# Ethernet.net
KiCad netlist of a schematic drawn in Altium Designer
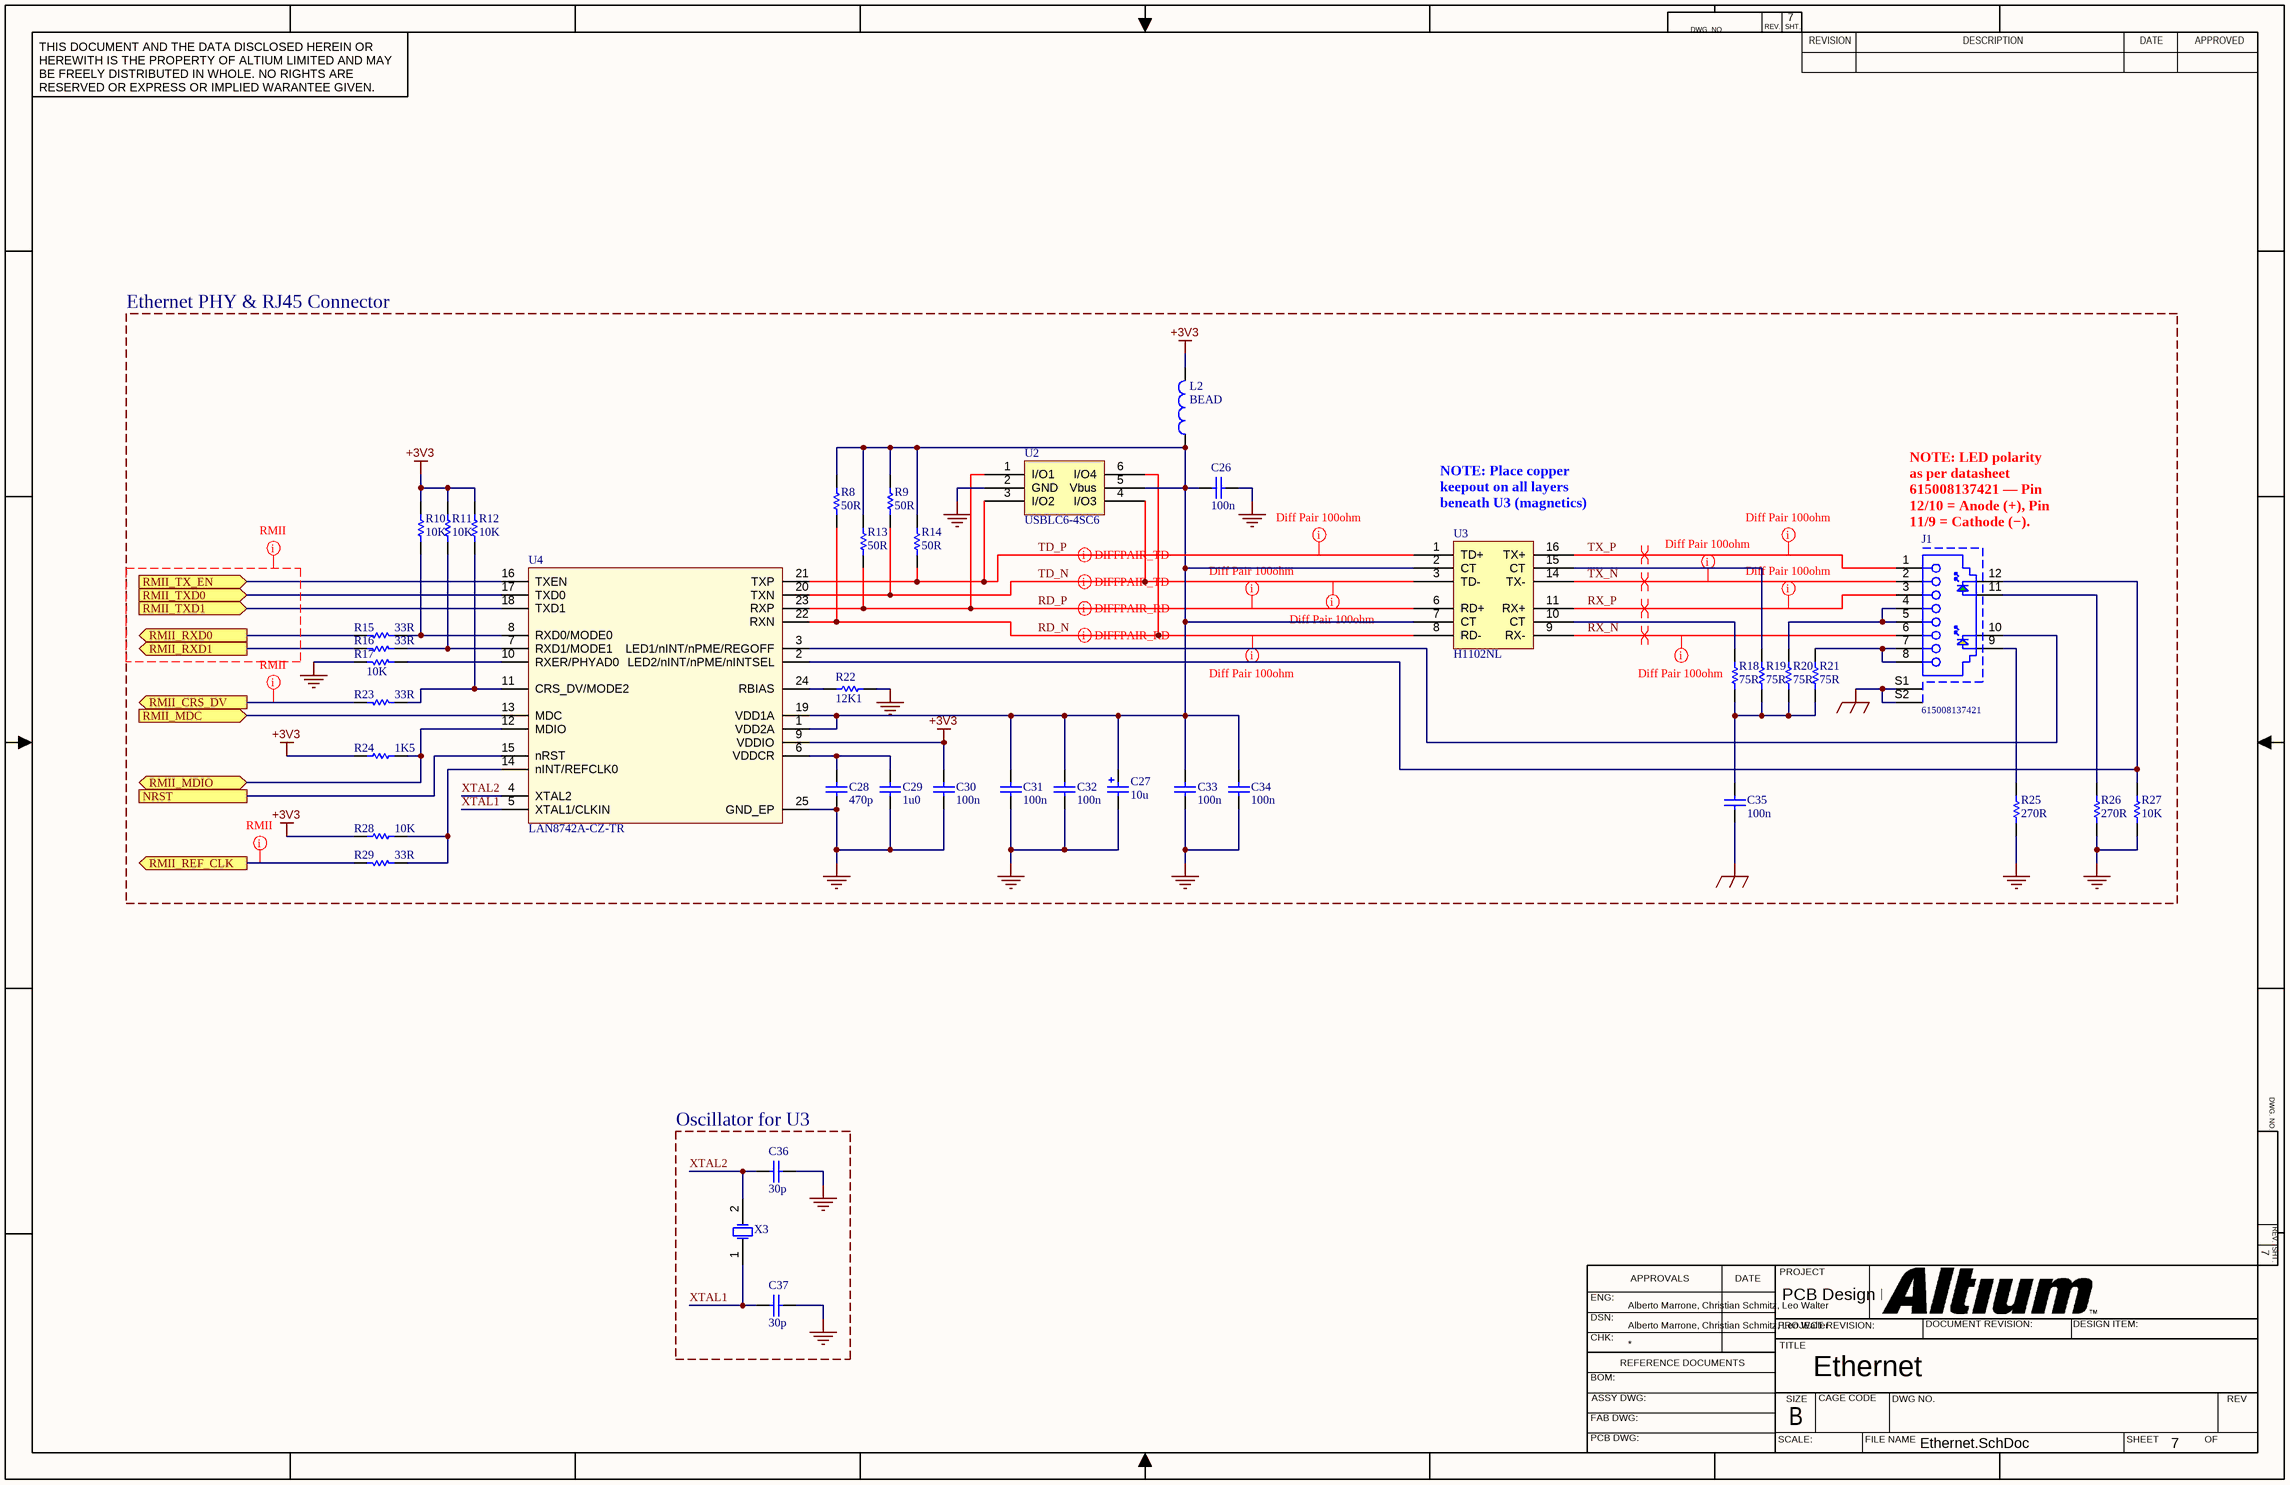
[diagram p0: Ethernet.SchDoc]

(export (version "E")
  (design (tool "Eeschema 10.0.6"))
  (components
    (comp (ref "C26")
      (value "100n")
      (footprint "0603C")
      (description "Capacitor")
      (fields (field (name "PUBLISHER") "Altium Limited"))
      (libsource (lib "Miscellaneous Devices") (part "Cap"))
    )
    (comp (ref "C27")
      (value "10u")
      (footprint "TAN-B")
      (description "Tantalum Capacitor")
      (fields (field (name "PUBLISHER") "Altium Limited"))
      (libsource (lib "Miscellaneous Devices") (part "Cap Pol1"))
    )
    (comp (ref "C28")
      (value "470p")
      (footprint "0603C")
      (description "Capacitor 0402 / 0603 / 0805")
      (libsource (lib "MCD_TOOLS") (part "Capacitor_ST"))
    )
    (comp (ref "C29")
      (value "1u0")
      (footprint "0603C")
      (description "Capacitor")
      (fields (field (name "TOLERANCE") "10%"))
      (libsource (lib "MB963_1") (part "CAP SMD 0603  X5R 1µF 25V 10%"))
    )
    (comp (ref "C30")
      (value "100n")
      (footprint "0603C")
      (description "Capacitor")
      (fields (field (name "PUBLISHER") "Altium Limited"))
      (libsource (lib "Miscellaneous Devices") (part "Cap"))
    )
    (comp (ref "C31")
      (value "100n")
      (footprint "0603C")
      (description "Capacitor")
      (fields (field (name "PUBLISHER") "Altium Limited"))
      (libsource (lib "Miscellaneous Devices") (part "Cap"))
    )
    (comp (ref "C32")
      (value "100n")
      (footprint "0603C")
      (description "Capacitor")
      (fields (field (name "PUBLISHER") "Altium Limited"))
      (libsource (lib "Miscellaneous Devices") (part "Cap"))
    )
    (comp (ref "C33")
      (value "100n")
      (footprint "0603C")
      (description "Capacitor")
      (fields (field (name "PUBLISHER") "Altium Limited"))
      (libsource (lib "Miscellaneous Devices") (part "Cap"))
    )
    (comp (ref "C34")
      (value "100n")
      (footprint "0603C")
      (description "Capacitor")
      (fields (field (name "PUBLISHER") "Altium Limited"))
      (libsource (lib "Miscellaneous Devices") (part "Cap"))
    )
    (comp (ref "C35")
      (value "100n")
      (footprint "0603C")
      (description "Capacitor")
      (fields (field (name "PUBLISHER") "Altium Limited"))
      (libsource (lib "Miscellaneous Devices") (part "Cap"))
    )
    (comp (ref "C36")
      (value "30p")
      (footprint "0603C")
      (description "Capacitor 0402 / 0603 / 0805")
      (libsource (lib "MCD_TOOLS") (part "Capacitor_ST"))
    )
    (comp (ref "C37")
      (value "30p")
      (footprint "0603C")
      (description "Capacitor 0402 / 0603 / 0805")
      (libsource (lib "MCD_TOOLS") (part "Capacitor_ST"))
    )
    (comp (ref "J1")
      (value "615008137421")
      (footprint "615008137421")
      (description "Modular Jack WR-MJ, Tab Up, Shielded, with LED and EMI Panel Finger, Horizontal Entry, THT, 8P8C")
      (fields (field (name "MANUFACTURER") "Wurth Elektronik") (field (name "PUBLISHER") "WurthElektronik"))
      (libsource (lib "Altium Content Vault") (part "WE-CN-1P-2F-J12_A"))
    )
    (comp (ref "L2")
      (value "BEAD")
      (footprint "0603L")
      (description "Inductor")
      (fields (field (name "PUBLISHER") "Altium Limited"))
      (libsource (lib "Miscellaneous Devices") (part "Inductor"))
    )
    (comp (ref "R8")
      (value "50R")
      (footprint "0603R")
      (description "Resistor,50,0603,1%,YAGEO")
      (libsource (lib "MB1137") (part "Res_50_1%_0603"))
    )
    (comp (ref "R9")
      (value "50R")
      (footprint "0603R")
      (description "Resistor,50,0603,1%,YAGEO")
      (libsource (lib "MB1137") (part "Res_50_1%_0603"))
    )
    (comp (ref "R10")
      (value "10K")
      (footprint "0603R")
      (description "Resistor")
      (fields (field (name "PUBLISHER") "Altium Limited"))
      (libsource (lib "Miscellaneous Devices") (part "res1"))
    )
    (comp (ref "R11")
      (value "10K")
      (footprint "0603R")
      (description "Resistor")
      (fields (field (name "PUBLISHER") "Altium Limited"))
      (libsource (lib "Miscellaneous Devices") (part "res1"))
    )
    (comp (ref "R12")
      (value "10K")
      (footprint "0603R")
      (description "Resistor")
      (fields (field (name "PUBLISHER") "Altium Limited"))
      (libsource (lib "Miscellaneous Devices") (part "res1"))
    )
    (comp (ref "R13")
      (value "50R")
      (footprint "0603R")
      (description "Resistor,50,0603,1%,YAGEO")
      (libsource (lib "MB1137") (part "Res_50_1%_0603"))
    )
    (comp (ref "R14")
      (value "50R")
      (footprint "0603R")
      (description "Resistor,50,0603,1%,YAGEO")
      (libsource (lib "MB1137") (part "Res_50_1%_0603"))
    )
    (comp (ref "R15")
      (value "33R")
      (footprint "0603R")
      (description "Resistor")
      (fields (field (name "TOLERANCE") "1%") (field (name "PUBLISHER") "Altium Limited"))
      (libsource (lib "Miscellaneous Devices") (part "res1"))
    )
    (comp (ref "R16")
      (value "33R")
      (footprint "0603R")
      (description "Resistor")
      (fields (field (name "TOLERANCE") "1%") (field (name "PUBLISHER") "Altium Limited"))
      (libsource (lib "Miscellaneous Devices") (part "res1"))
    )
    (comp (ref "R17")
      (value "10K")
      (footprint "0603R")
      (description "Resistor")
      (fields (field (name "PUBLISHER") "Altium Limited"))
      (libsource (lib "Miscellaneous Devices") (part "res1"))
    )
    (comp (ref "R18")
      (value "75R")
      (footprint "0603R")
      (description "Resistor")
      (fields (field (name "TOLERANCE") "1%"))
      (libsource (lib "MB1137") (part "Res_75_1%_0603"))
    )
    (comp (ref "R19")
      (value "75R")
      (footprint "0603R")
      (description "Resistor")
      (fields (field (name "TOLERANCE") "1%"))
      (libsource (lib "MB1137") (part "Res_75_1%_0603"))
    )
    (comp (ref "R20")
      (value "75R")
      (footprint "0603R")
      (description "Resistor")
      (fields (field (name "TOLERANCE") "1%"))
      (libsource (lib "MB1137") (part "Res_75_1%_0603"))
    )
    (comp (ref "R21")
      (value "75R")
      (footprint "0603R")
      (description "Resistor")
      (fields (field (name "TOLERANCE") "1%"))
      (libsource (lib "MB1137") (part "Res_75_1%_0603"))
    )
    (comp (ref "R22")
      (value "12K1")
      (footprint "0603R")
      (description "Resistor,12K1,0603,1%,VISHAY")
      (libsource (lib "MCD_TOOLS") (part "Res_12K1_1%_0603"))
    )
    (comp (ref "R23")
      (value "33R")
      (footprint "0603R")
      (description "Resistor")
      (fields (field (name "TOLERANCE") "1%") (field (name "PUBLISHER") "Altium Limited"))
      (libsource (lib "Miscellaneous Devices") (part "res1"))
    )
    (comp (ref "R24")
      (value "1K5")
      (footprint "0603R")
      (description "Resistor,1K5,0402,1%,YAGEO")
      (libsource (lib "MCD_TOOLS") (part "Res_1K5_1%_0402"))
    )
    (comp (ref "R25")
      (value "270R")
      (footprint "0603R")
      (description "Resistor 0402 / 0603 / 0805")
      (libsource (lib "Miscellaneous Devices") (part "Res1"))
    )
    (comp (ref "R26")
      (value "270R")
      (footprint "0603R")
      (description "Resistor 0402 / 0603 / 0805")
      (libsource (lib "Miscellaneous Devices") (part "Res1"))
    )
    (comp (ref "R27")
      (value "10K")
      (footprint "0603R")
      (description "Resistor")
      (fields (field (name "PUBLISHER") "Altium Limited"))
      (libsource (lib "Miscellaneous Devices") (part "res1"))
    )
    (comp (ref "R28")
      (value "10K")
      (footprint "0603R")
      (description "Resistor")
      (fields (field (name "PUBLISHER") "Altium Limited"))
      (libsource (lib "Miscellaneous Devices") (part "res1"))
    )
    (comp (ref "R29")
      (value "33R")
      (footprint "0603R")
      (description "Resistor")
      (fields (field (name "TOLERANCE") "1%") (field (name "PUBLISHER") "Altium Limited"))
      (libsource (lib "Miscellaneous Devices") (part "res1"))
    )
    (comp (ref "U2")
      (value "USBLC6-4SC6")
      (footprint "SOT23-6L")
      (libsource (lib "MB1137_1") (part "USBLC6-4SC6"))
    )
    (comp (ref "U3")
      (value "H1102NL")
      (footprint "Transformer")
      (description "replaces the KMS-1102NL")
      (libsource (lib "MB1137") (part "KMS-1102NL"))
    )
    (comp (ref "U4")
      (value "LAN8742A-CZ-TR")
      (footprint "QFN24_0R5_4X4")
      (libsource (lib "MB1137") (part "LAN8742A-CZ-TR"))
    )
    (comp (ref "X3")
      (value "ECS-250-12-30Q-JES-TR")
      (footprint "XTAL_2SM_5R0X3R2")
      (description "Crystal Oscillator")
      (fields (field (name "PUBLISHER") "Altium Limited"))
      (libsource (lib "MB1137") (part "XTAL_5032"))
    )
  )
  (nets
    (net (code "1") (name "+3V3") (class "Default")
      (node (ref "C30") (pin "2") (pinfunction "2_2") (pintype "passive"))
      (node (ref "L2") (pin "2") (pinfunction "2_2") (pintype "passive"))
      (node (ref "R10") (pin "1") (pinfunction "1_1") (pintype "passive"))
      (node (ref "R11") (pin "1") (pinfunction "1_1") (pintype "passive"))
      (node (ref "R12") (pin "1") (pinfunction "1_1") (pintype "passive"))
      (node (ref "R24") (pin "2") (pinfunction "2_2") (pintype "passive"))
      (node (ref "R28") (pin "1") (pinfunction "1_1") (pintype "passive"))
      (node (ref "U4") (pin "9") (pinfunction "VDDIO_9") (pintype "passive"))
    )
    (net (code "2") (name "/NRST") (class "Default")
      (node (ref "U4") (pin "15") (pinfunction "nRST_15") (pintype "passive"))
    )
    (net (code "3") (name "/RD_N") (class "Default")
      (node (ref "R8") (pin "1") (pinfunction "1_1") (pintype "passive"))
      (node (ref "U2") (pin "6") (pinfunction "I/O4_6") (pintype "passive"))
      (node (ref "U3") (pin "8") (pinfunction "RD-_8") (pintype "passive"))
      (node (ref "U4") (pin "22") (pinfunction "RXN_22") (pintype "passive"))
    )
    (net (code "4") (name "/RD_P") (class "Default")
      (node (ref "R13") (pin "1") (pinfunction "1_1") (pintype "passive"))
      (node (ref "U2") (pin "1") (pinfunction "I/O1_1") (pintype "passive"))
      (node (ref "U3") (pin "6") (pinfunction "RD+_6") (pintype "passive"))
      (node (ref "U4") (pin "23") (pinfunction "RXP_23") (pintype "passive"))
    )
    (net (code "5") (name "/RMII_CRS_DV") (class "Default")
      (node (ref "R23") (pin "2") (pinfunction "2_2") (pintype "passive"))
    )
    (net (code "6") (name "/RMII_MDC") (class "Default")
      (node (ref "U4") (pin "13") (pinfunction "MDC_13") (pintype "passive"))
    )
    (net (code "7") (name "/RMII_MDIO") (class "Default")
      (node (ref "R24") (pin "1") (pinfunction "1_1") (pintype "passive"))
      (node (ref "U4") (pin "12") (pinfunction "MDIO_12") (pintype "passive"))
    )
    (net (code "8") (name "/RMII_REF_CLK") (class "Default")
      (node (ref "R29") (pin "2") (pinfunction "2_2") (pintype "passive"))
    )
    (net (code "9") (name "/RMII_RXD0") (class "Default")
      (node (ref "R15") (pin "2") (pinfunction "2_2") (pintype "passive"))
    )
    (net (code "10") (name "/RMII_RXD1") (class "Default")
      (node (ref "R16") (pin "2") (pinfunction "2_2") (pintype "passive"))
    )
    (net (code "11") (name "/RMII_TXD0") (class "Default")
      (node (ref "U4") (pin "17") (pinfunction "TXD0_17") (pintype "passive"))
    )
    (net (code "12") (name "/RMII_TXD1") (class "Default")
      (node (ref "U4") (pin "18") (pinfunction "TXD1_18") (pintype "passive"))
    )
    (net (code "13") (name "/RMII_TX_EN") (class "Default")
      (node (ref "U4") (pin "16") (pinfunction "TXEN_16") (pintype "passive"))
    )
    (net (code "14") (name "/RX_N") (class "Default")
      (node (ref "J1") (pin "6") (pinfunction "6_6") (pintype "passive"))
      (node (ref "U3") (pin "9") (pinfunction "RX-_9") (pintype "passive"))
    )
    (net (code "15") (name "/RX_P") (class "Default")
      (node (ref "J1") (pin "3") (pinfunction "3_3") (pintype "passive"))
      (node (ref "U3") (pin "11") (pinfunction "RX+_11") (pintype "passive"))
    )
    (net (code "16") (name "/TD_N") (class "Default")
      (node (ref "R9") (pin "1") (pinfunction "1_1") (pintype "passive"))
      (node (ref "U2") (pin "4") (pinfunction "I/O3_4") (pintype "passive"))
      (node (ref "U3") (pin "3") (pinfunction "TD-_3") (pintype "passive"))
      (node (ref "U4") (pin "20") (pinfunction "TXN_20") (pintype "passive"))
    )
    (net (code "17") (name "/TD_P") (class "Default")
      (node (ref "R14") (pin "1") (pinfunction "1_1") (pintype "passive"))
      (node (ref "U2") (pin "3") (pinfunction "I/O2_3") (pintype "passive"))
      (node (ref "U3") (pin "1") (pinfunction "TD+_1") (pintype "passive"))
      (node (ref "U4") (pin "21") (pinfunction "TXP_21") (pintype "passive"))
    )
    (net (code "18") (name "/TX_N") (class "Default")
      (node (ref "J1") (pin "2") (pinfunction "2_2") (pintype "passive"))
      (node (ref "U3") (pin "14") (pinfunction "TX-_14") (pintype "passive"))
    )
    (net (code "19") (name "/TX_P") (class "Default")
      (node (ref "J1") (pin "1") (pinfunction "1_1") (pintype "passive"))
      (node (ref "U3") (pin "16") (pinfunction "TX+_16") (pintype "passive"))
    )
    (net (code "20") (name "/XTAL1") (class "Default")
      (node (ref "C37") (pin "1") (pinfunction "1_1") (pintype "passive"))
      (node (ref "U4") (pin "5") (pinfunction "XTAL1/CLKIN_5") (pintype "passive"))
      (node (ref "X3") (pin "1") (pinfunction "OSC1_1") (pintype "passive"))
    )
    (net (code "21") (name "/XTAL2") (class "Default")
      (node (ref "C36") (pin "1") (pinfunction "1_1") (pintype "passive"))
      (node (ref "U4") (pin "4") (pinfunction "XTAL2_4") (pintype "passive"))
      (node (ref "X3") (pin "2") (pinfunction "OSC2_2") (pintype "passive"))
    )
    (net (code "22") (name "EGND") (class "Default")
      (node (ref "C35") (pin "1") (pinfunction "1_1") (pintype "passive"))
      (node (ref "J1") (pin "S1") (pinfunction "S1_S1") (pintype "passive"))
      (node (ref "J1") (pin "S2") (pinfunction "S2_S2") (pintype "passive"))
    )
    (net (code "23") (name "GND") (class "Default")
      (node (ref "C26") (pin "1") (pinfunction "1_1") (pintype "passive"))
      (node (ref "C27") (pin "2") (pinfunction "2_2") (pintype "passive"))
      (node (ref "C28") (pin "1") (pinfunction "1_1") (pintype "passive"))
      (node (ref "C29") (pin "2") (pinfunction "2_2") (pintype "passive"))
      (node (ref "C30") (pin "1") (pinfunction "1_1") (pintype "passive"))
      (node (ref "C31") (pin "1") (pinfunction "1_1") (pintype "passive"))
      (node (ref "C32") (pin "1") (pinfunction "1_1") (pintype "passive"))
      (node (ref "C33") (pin "1") (pinfunction "1_1") (pintype "passive"))
      (node (ref "C34") (pin "1") (pinfunction "1_1") (pintype "passive"))
      (node (ref "C36") (pin "2") (pinfunction "2_2") (pintype "passive"))
      (node (ref "C37") (pin "2") (pinfunction "2_2") (pintype "passive"))
      (node (ref "R17") (pin "2") (pinfunction "2_2") (pintype "passive"))
      (node (ref "R22") (pin "2") (pinfunction "2_2") (pintype "passive"))
      (node (ref "R25") (pin "2") (pinfunction "2_2") (pintype "passive"))
      (node (ref "R26") (pin "2") (pinfunction "2_2") (pintype "passive"))
      (node (ref "R27") (pin "2") (pinfunction "2_2") (pintype "passive"))
      (node (ref "U2") (pin "2") (pinfunction "GND_2") (pintype "passive"))
      (node (ref "U4") (pin "25") (pinfunction "GND_EP_25") (pintype "passive"))
    )
    (net (code "24") (name "Net-(C35-Pad2)") (class "Default")
      (node (ref "C35") (pin "2") (pinfunction "2_2") (pintype "passive"))
      (node (ref "R18") (pin "1") (pinfunction "1_1") (pintype "passive"))
      (node (ref "R19") (pin "1") (pinfunction "1_1") (pintype "passive"))
      (node (ref "R20") (pin "1") (pinfunction "1_1") (pintype "passive"))
      (node (ref "R21") (pin "1") (pinfunction "1_1") (pintype "passive"))
    )
    (net (code "25") (name "Net-(J1-Pad4)") (class "Default")
      (node (ref "J1") (pin "4") (pinfunction "4_4") (pintype "passive"))
      (node (ref "J1") (pin "5") (pinfunction "5_5") (pintype "passive"))
      (node (ref "R20") (pin "2") (pinfunction "2_2") (pintype "passive"))
    )
    (net (code "26") (name "Net-(J1-Pad7)") (class "Default")
      (node (ref "J1") (pin "7") (pinfunction "7_7") (pintype "passive"))
      (node (ref "J1") (pin "8") (pinfunction "8_8") (pintype "passive"))
      (node (ref "R21") (pin "2") (pinfunction "2_2") (pintype "passive"))
    )
    (net (code "27") (name "Net-(J1-Pad9)") (class "Default")
      (node (ref "J1") (pin "9") (pinfunction "9_9") (pintype "passive"))
      (node (ref "R25") (pin "1") (pinfunction "1_1") (pintype "passive"))
    )
    (net (code "28") (name "Net-(J1-Pad11)") (class "Default")
      (node (ref "J1") (pin "11") (pinfunction "11_11") (pintype "passive"))
      (node (ref "R26") (pin "1") (pinfunction "1_1") (pintype "passive"))
    )
    (net (code "29") (name "Net-(R18-Pad2)") (class "Default")
      (node (ref "R18") (pin "2") (pinfunction "2_2") (pintype "passive"))
      (node (ref "U3") (pin "10") (pinfunction "CT_10") (pintype "passive"))
    )
    (net (code "30") (name "Net-(R19-Pad2)") (class "Default")
      (node (ref "R19") (pin "2") (pinfunction "2_2") (pintype "passive"))
      (node (ref "U3") (pin "15") (pinfunction "CT_15") (pintype "passive"))
    )
    (net (code "31") (name "Net-(U2-Vbus)") (class "Default")
      (node (ref "C26") (pin "2") (pinfunction "2_2") (pintype "passive"))
      (node (ref "C27") (pin "1") (pinfunction "1_1") (pintype "passive"))
      (node (ref "C31") (pin "2") (pinfunction "2_2") (pintype "passive"))
      (node (ref "C32") (pin "2") (pinfunction "2_2") (pintype "passive"))
      (node (ref "C33") (pin "2") (pinfunction "2_2") (pintype "passive"))
      (node (ref "C34") (pin "2") (pinfunction "2_2") (pintype "passive"))
      (node (ref "L2") (pin "1") (pinfunction "1_1") (pintype "passive"))
      (node (ref "R13") (pin "2") (pinfunction "2_2") (pintype "passive"))
      (node (ref "R14") (pin "2") (pinfunction "2_2") (pintype "passive"))
      (node (ref "R8") (pin "2") (pinfunction "2_2") (pintype "passive"))
      (node (ref "R9") (pin "2") (pinfunction "2_2") (pintype "passive"))
      (node (ref "U2") (pin "5") (pinfunction "Vbus_5") (pintype "passive"))
      (node (ref "U3") (pin "2") (pinfunction "CT_2") (pintype "passive"))
      (node (ref "U3") (pin "7") (pinfunction "CT_7") (pintype "passive"))
      (node (ref "U4") (pin "1") (pinfunction "VDD2A_1") (pintype "passive"))
      (node (ref "U4") (pin "19") (pinfunction "VDD1A_19") (pintype "passive"))
    )
    (net (code "32") (name "Net-(U4-CRS_DV{slash}MODE2)") (class "Default")
      (node (ref "R12") (pin "2") (pinfunction "2_2") (pintype "passive"))
      (node (ref "R23") (pin "1") (pinfunction "1_1") (pintype "passive"))
      (node (ref "U4") (pin "11") (pinfunction "CRS_DV/MODE2_11") (pintype "passive"))
    )
    (net (code "33") (name "Net-(U4-LED1{slash}nINT{slash}nPME{slash}REGOFF)") (class "Default")
      (node (ref "J1") (pin "10") (pinfunction "10_10") (pintype "passive"))
      (node (ref "U4") (pin "3") (pinfunction "LED1/nINT/nPME/REGOFF_3") (pintype "passive"))
    )
    (net (code "34") (name "Net-(U4-LED2{slash}nINT{slash}nPME{slash}nINTSEL)") (class "Default")
      (node (ref "J1") (pin "12") (pinfunction "12_12") (pintype "passive"))
      (node (ref "R27") (pin "1") (pinfunction "1_1") (pintype "passive"))
      (node (ref "U4") (pin "2") (pinfunction "LED2/nINT/nPME/nINTSEL_2") (pintype "passive"))
    )
    (net (code "35") (name "Net-(U4-RBIAS)") (class "Default")
      (node (ref "R22") (pin "1") (pinfunction "1_1") (pintype "passive"))
      (node (ref "U4") (pin "24") (pinfunction "RBIAS_24") (pintype "passive"))
    )
    (net (code "36") (name "Net-(U4-RXD0{slash}MODE0)") (class "Default")
      (node (ref "R10") (pin "2") (pinfunction "2_2") (pintype "passive"))
      (node (ref "R15") (pin "1") (pinfunction "1_1") (pintype "passive"))
      (node (ref "U4") (pin "8") (pinfunction "RXD0/MODE0_8") (pintype "passive"))
    )
    (net (code "37") (name "Net-(U4-RXD1{slash}MODE1)") (class "Default")
      (node (ref "R11") (pin "2") (pinfunction "2_2") (pintype "passive"))
      (node (ref "R16") (pin "1") (pinfunction "1_1") (pintype "passive"))
      (node (ref "U4") (pin "7") (pinfunction "RXD1/MODE1_7") (pintype "passive"))
    )
    (net (code "38") (name "Net-(U4-RXER{slash}PHYAD0)") (class "Default")
      (node (ref "R17") (pin "1") (pinfunction "1_1") (pintype "passive"))
      (node (ref "U4") (pin "10") (pinfunction "RXER/PHYAD0_10") (pintype "passive"))
    )
    (net (code "39") (name "Net-(U4-VDDCR)") (class "Default")
      (node (ref "C28") (pin "2") (pinfunction "2_2") (pintype "passive"))
      (node (ref "C29") (pin "1") (pinfunction "1_1") (pintype "passive"))
      (node (ref "U4") (pin "6") (pinfunction "VDDCR_6") (pintype "passive"))
    )
    (net (code "40") (name "Net-(U4-nINT{slash}REFCLK0)") (class "Default")
      (node (ref "R28") (pin "2") (pinfunction "2_2") (pintype "passive"))
      (node (ref "R29") (pin "1") (pinfunction "1_1") (pintype "passive"))
      (node (ref "U4") (pin "14") (pinfunction "nINT/REFCLK0_14") (pintype "passive"))
    )
  )
)
